# CON_AUDIO_AC99.net
KiCad netlist of a schematic drawn in Altium Designer
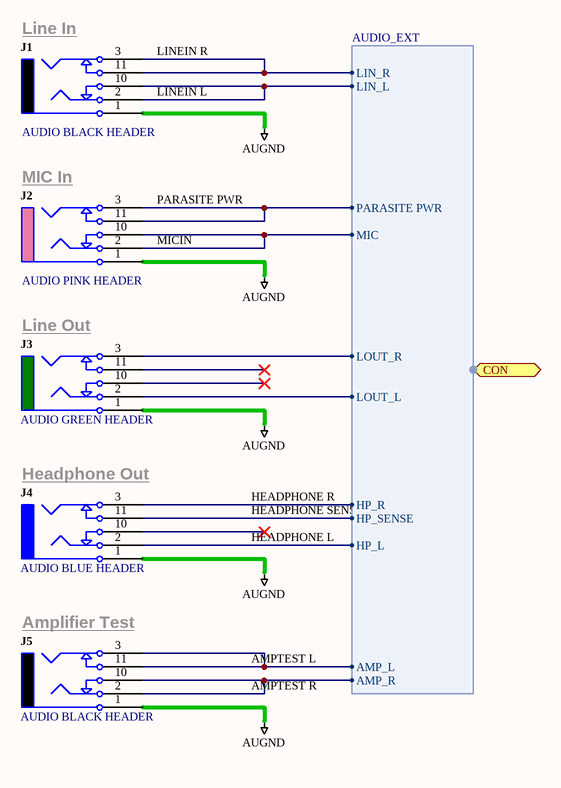
[diagram p0: CON_AUDIO_AC99.SchDoc]

(export (version "E")
  (design (tool "Eeschema 10.0.6"))
  (components
    (comp (ref "J1")
      (value "AUDIO BLACK HEADER")
      (footprint "TSH-3675")
      (libsource (lib "altium-import") (part "root_0_CON-PHONEJACK_"))
    )
    (comp (ref "J2")
      (value "AUDIO PINK HEADER")
      (footprint "TSH-3675")
      (libsource (lib "altium-import") (part "root_0_CON-PHONEJACK_"))
    )
    (comp (ref "J3")
      (value "AUDIO GREEN HEADER")
      (footprint "TSH-3675")
      (libsource (lib "altium-import") (part "root_0_CON-PHONEJACK_"))
    )
    (comp (ref "J4")
      (value "AUDIO BLUE HEADER")
      (footprint "TSH-3675")
      (libsource (lib "altium-import") (part "root_0_CON-PHONEJACK_"))
    )
    (comp (ref "J5")
      (value "AUDIO BLACK HEADER")
      (footprint "TSH-3675")
      (libsource (lib "altium-import") (part "root_0_CON-PHONEJACK_"))
    )
  )
  (nets
    (net (code "2") (name "/AMP_L") (class "Default")
      (node (ref "J5") (pin "11") (pintype "passive"))
      (node (ref "J5") (pin "3") (pintype "passive"))
    )
    (net (code "3") (name "/AMP_R") (class "Default")
      (node (ref "J5") (pin "10") (pintype "passive"))
      (node (ref "J5") (pin "2") (pintype "passive"))
    )
    (net (code "4") (name "/HP_L") (class "Default") (node (ref "J4") (pin "2") (pintype "passive")))
    (net (code "5") (name "/HP_R") (class "Default") (node (ref "J4") (pin "3") (pintype "passive")))
    (net (code "6") (name "/HP_SENSE") (class "Default") (node (ref "J4") (pin "11") (pintype "passive")))
    (net (code "7") (name "/LIN_L") (class "Default")
      (node (ref "J1") (pin "10") (pintype "passive"))
      (node (ref "J1") (pin "2") (pintype "passive"))
    )
    (net (code "8") (name "/LIN_R") (class "Default")
      (node (ref "J1") (pin "11") (pintype "passive"))
      (node (ref "J1") (pin "3") (pintype "passive"))
    )
    (net (code "9") (name "/LOUT_L") (class "Default") (node (ref "J3") (pin "2") (pintype "passive")))
    (net (code "10") (name "/LOUT_R") (class "Default") (node (ref "J3") (pin "3") (pintype "passive")))
    (net (code "11") (name "/MIC") (class "Default")
      (node (ref "J2") (pin "10") (pintype "passive"))
      (node (ref "J2") (pin "2") (pintype "passive"))
    )
    (net (code "12") (name "/PARASITE PWR") (class "Default")
      (node (ref "J2") (pin "11") (pintype "passive"))
      (node (ref "J2") (pin "3") (pintype "passive"))
    )
    (net (code "14") (name "AUGND") (class "Default")
      (node (ref "J1") (pin "1") (pintype "passive"))
      (node (ref "J2") (pin "1") (pintype "passive"))
      (node (ref "J3") (pin "1") (pintype "passive"))
      (node (ref "J4") (pin "1") (pintype "passive"))
      (node (ref "J5") (pin "1") (pintype "passive"))
    )
    (net (code "15") (name "unconnected-(J3-Pad10)") (class "Default")
      (node (ref "J3") (pin "10") (pintype "passive+no_connect"))
    )
    (net (code "16") (name "unconnected-(J3-Pad11)") (class "Default")
      (node (ref "J3") (pin "11") (pintype "passive+no_connect"))
    )
    (net (code "17") (name "unconnected-(J4-Pad10)") (class "Default")
      (node (ref "J4") (pin "10") (pintype "passive+no_connect"))
    )
  )
)
